# P20-Receptor_Transmisor_NRF24I01.net
KiCad netlist of a schematic drawn in EAGLE
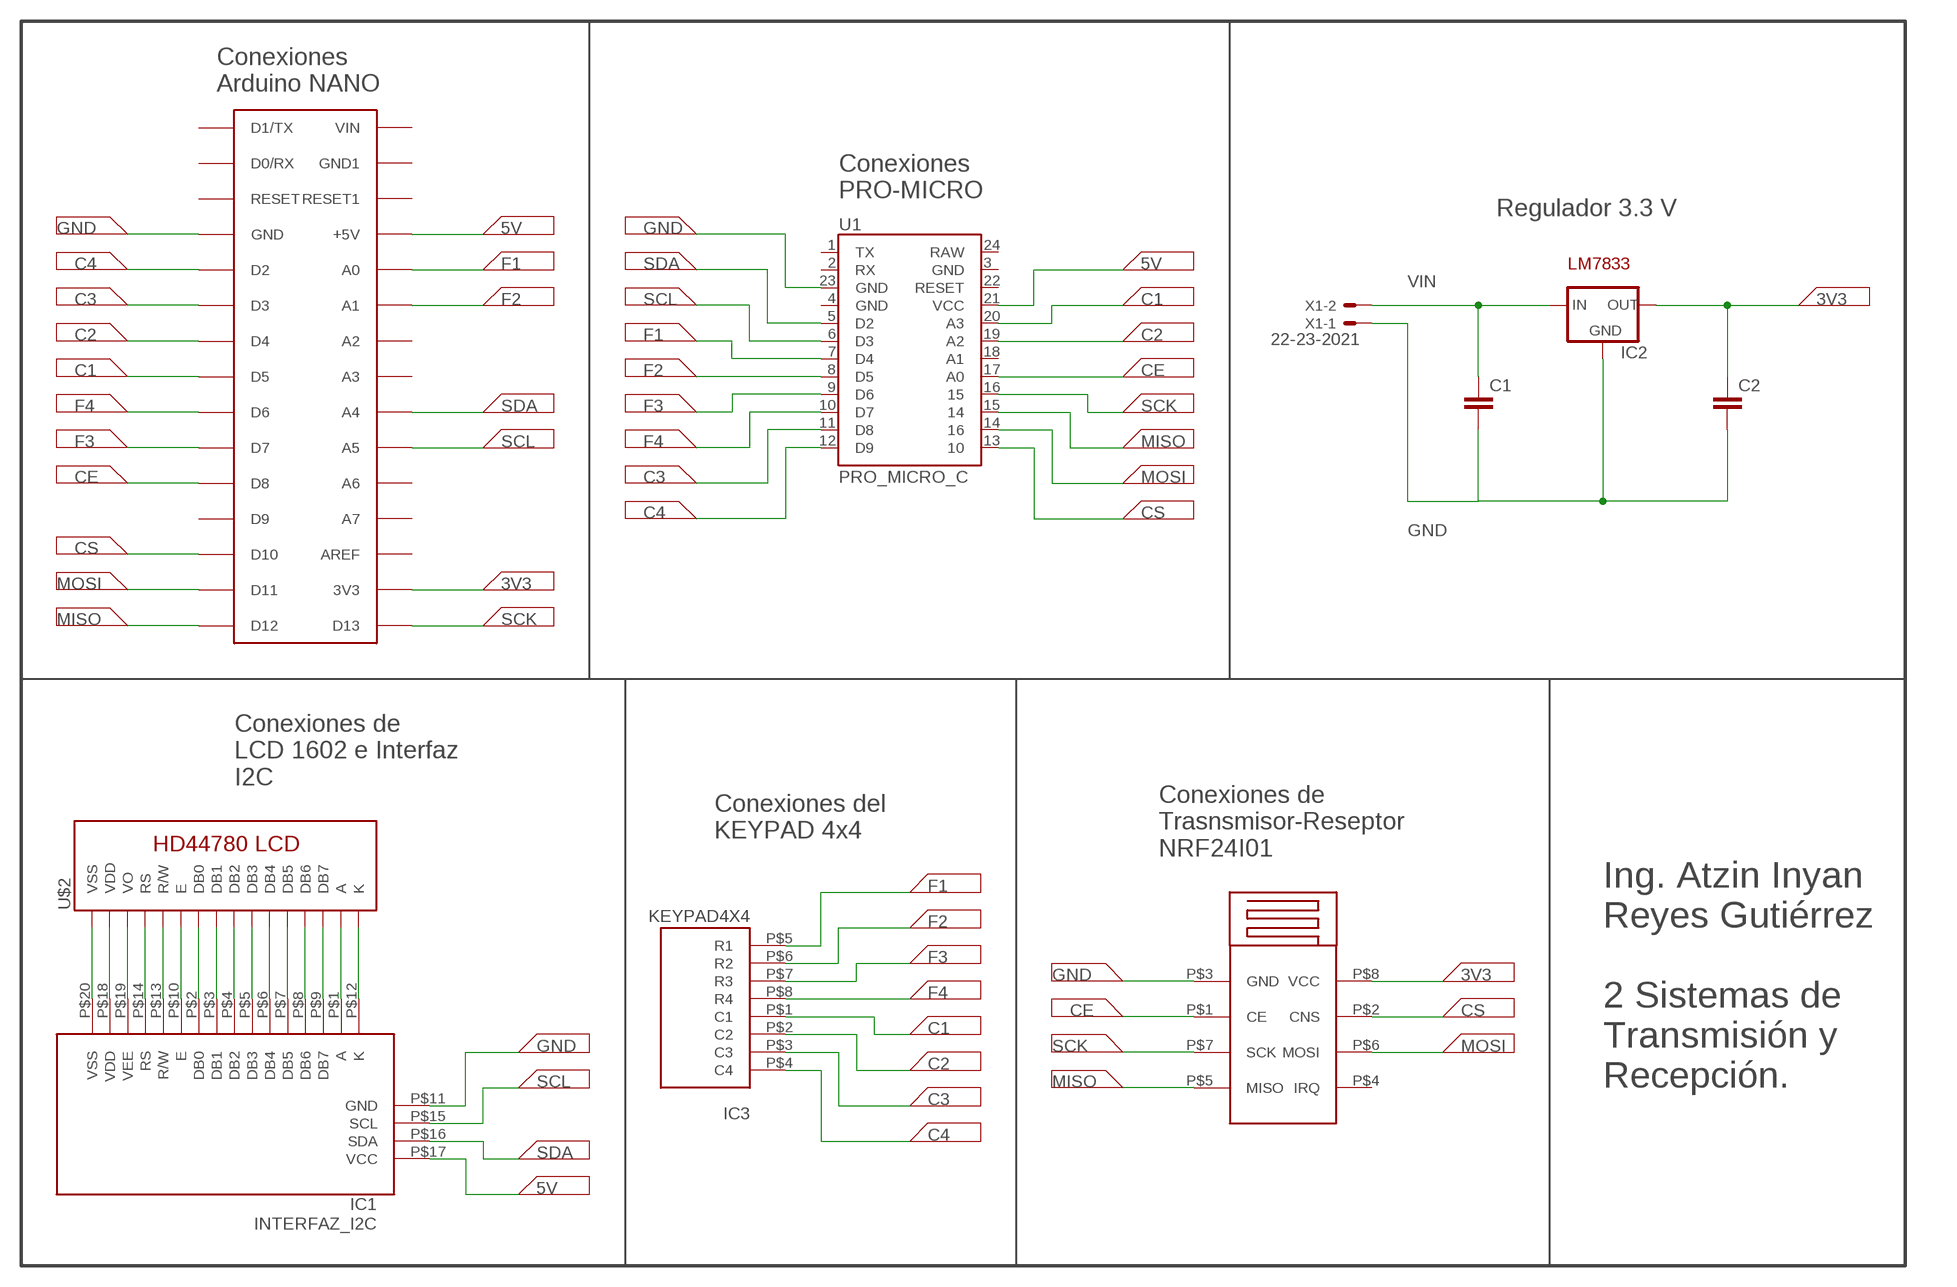
[diagram p0: schematic, sheet 1]

(export (version "E")
  (design (tool "Eeschema 10.0.6"))
  (components
    (comp (ref "C1")
      (value "C2,5-3")
      (footprint "eagle-import:C2.5-3")
      (libsource (lib "eagle-import") (part "C2,5-3"))
    )
    (comp (ref "C2")
      (value "C2,5-3")
      (footprint "eagle-import:C2.5-3")
      (libsource (lib "eagle-import") (part "C2,5-3"))
    )
    (comp (ref "IC1")
      (value "INTERFAZ_I2C")
      (footprint "eagle-import:NO_FOOTPRINT")
      (libsource (lib "eagle-import") (part "INTERFAZ_I2C"))
    )
    (comp (ref "IC2")
      (value "78MXXL")
      (footprint "eagle-import:78MXXL")
      (libsource (lib "eagle-import") (part "78MXXL"))
    )
    (comp (ref "IC3")
      (value "KEYPAD4X4")
      (footprint "eagle-import:NO_FOOTPRINT")
      (libsource (lib "eagle-import") (part "KEYPAD4X4"))
    )
    (comp (ref "U$1")
      (value "ARDUINONANO")
      (footprint "eagle-import:PDIP-32")
      (libsource (lib "eagle-import") (part "ARDUINONANO"))
    )
    (comp (ref "U$2")
      (value "LCD-HD447803-HOLES16X2-3-HOLES")
      (footprint "eagle-import:LCD-16X2-3HOLES")
      (libsource (lib "eagle-import") (part "LCD-HD4478016X2-3-HOLES3-HOLES"))
    )
    (comp (ref "U$3")
      (value "NRF24I01")
      (footprint "eagle-import:NOT_FOOTPRINT")
      (libsource (lib "eagle-import") (part "NRF24I01"))
    )
    (comp (ref "U1")
      (value "PRO_MICRO_C")
      (footprint "eagle-import:PRO_MICRO_C")
      (libsource (lib "eagle-import") (part "PRO_MICRO_C"))
    )
    (comp (ref "X1")
      (value "22-23-2021")
      (footprint "eagle-import:22-23-2021")
      (fields (field (name "MF") "MOLEX"))
      (libsource (lib "eagle-import") (part "22-23-2021"))
    )
  )
  (nets
    (net (code "1") (name "/3V3") (class "Default")
      (node (ref "C2") (pin "1") (pinfunction "1_1") (pintype "passive"))
      (node (ref "IC2") (pin "OUT") (pinfunction "OUT_OUT") (pintype "passive"))
      (node (ref "U$1") (pin "3V3") (pinfunction "3V3_3V3") (pintype "bidirectional"))
      (node (ref "U$3") (pin "P$8") (pinfunction "VCC_P$8") (pintype "bidirectional"))
    )
    (net (code "2") (name "/5V") (class "Default")
      (node (ref "IC1") (pin "P$17") (pinfunction "VCC_P$17") (pintype "bidirectional"))
      (node (ref "U$1") (pin "+5V") (pinfunction "+5V_+5V") (pintype "bidirectional"))
      (node (ref "U1") (pin "21") (pinfunction "VCC_21") (pintype "bidirectional"))
    )
    (net (code "3") (name "/C1") (class "Default")
      (node (ref "IC3") (pin "P$1") (pinfunction "C1_P$1") (pintype "bidirectional"))
      (node (ref "U$1") (pin "D5") (pinfunction "D5_D5") (pintype "bidirectional"))
      (node (ref "U1") (pin "20") (pinfunction "A3_20") (pintype "bidirectional"))
    )
    (net (code "4") (name "/C2") (class "Default")
      (node (ref "IC3") (pin "P$2") (pinfunction "C2_P$2") (pintype "bidirectional"))
      (node (ref "U$1") (pin "D4") (pinfunction "D4_D4") (pintype "bidirectional"))
      (node (ref "U1") (pin "19") (pinfunction "A2_19") (pintype "bidirectional"))
    )
    (net (code "5") (name "/C3") (class "Default")
      (node (ref "IC3") (pin "P$3") (pinfunction "C3_P$3") (pintype "bidirectional"))
      (node (ref "U$1") (pin "D3") (pinfunction "D3_D3") (pintype "bidirectional"))
      (node (ref "U1") (pin "11") (pinfunction "D8_11") (pintype "bidirectional"))
    )
    (net (code "6") (name "/C4") (class "Default")
      (node (ref "IC3") (pin "P$4") (pinfunction "C4_P$4") (pintype "bidirectional"))
      (node (ref "U$1") (pin "D2") (pinfunction "D2_D2") (pintype "bidirectional"))
      (node (ref "U1") (pin "12") (pinfunction "D9_12") (pintype "bidirectional"))
    )
    (net (code "7") (name "/CE") (class "Default")
      (node (ref "U$1") (pin "D8") (pinfunction "D8_D8") (pintype "bidirectional"))
      (node (ref "U$3") (pin "P$1") (pinfunction "CE_P$1") (pintype "bidirectional"))
      (node (ref "U1") (pin "17") (pinfunction "A0_17") (pintype "bidirectional"))
    )
    (net (code "8") (name "/CS") (class "Default")
      (node (ref "U$1") (pin "D10") (pinfunction "D10_D10") (pintype "bidirectional"))
      (node (ref "U$3") (pin "P$2") (pinfunction "CNS_P$2") (pintype "bidirectional"))
      (node (ref "U1") (pin "13") (pinfunction "10_13") (pintype "bidirectional"))
    )
    (net (code "9") (name "/F1") (class "Default")
      (node (ref "IC3") (pin "P$5") (pinfunction "R1_P$5") (pintype "bidirectional"))
      (node (ref "U$1") (pin "A0") (pinfunction "A0_A0") (pintype "bidirectional"))
      (node (ref "U1") (pin "7") (pinfunction "D4_7") (pintype "bidirectional"))
    )
    (net (code "10") (name "/F2") (class "Default")
      (node (ref "IC3") (pin "P$6") (pinfunction "R2_P$6") (pintype "bidirectional"))
      (node (ref "U$1") (pin "A1") (pinfunction "A1_A1") (pintype "bidirectional"))
      (node (ref "U1") (pin "8") (pinfunction "D5_8") (pintype "bidirectional"))
    )
    (net (code "11") (name "/F3") (class "Default")
      (node (ref "IC3") (pin "P$7") (pinfunction "R3_P$7") (pintype "bidirectional"))
      (node (ref "U$1") (pin "D7") (pinfunction "D7_D7") (pintype "bidirectional"))
      (node (ref "U1") (pin "9") (pinfunction "D6_9") (pintype "bidirectional"))
    )
    (net (code "12") (name "/F4") (class "Default")
      (node (ref "IC3") (pin "P$8") (pinfunction "R4_P$8") (pintype "bidirectional"))
      (node (ref "U$1") (pin "D6") (pinfunction "D6_D6") (pintype "bidirectional"))
      (node (ref "U1") (pin "10") (pinfunction "D7_10") (pintype "bidirectional"))
    )
    (net (code "13") (name "/GND") (class "Default")
      (node (ref "C1") (pin "2") (pinfunction "2_2") (pintype "passive"))
      (node (ref "C2") (pin "2") (pinfunction "2_2") (pintype "passive"))
      (node (ref "IC1") (pin "P$11") (pinfunction "GND_P$11") (pintype "bidirectional"))
      (node (ref "IC2") (pin "GND") (pinfunction "GND_GND") (pintype "input"))
      (node (ref "U$1") (pin "GND") (pinfunction "GND_GND") (pintype "bidirectional"))
      (node (ref "U$3") (pin "P$3") (pinfunction "GND_P$3") (pintype "bidirectional"))
      (node (ref "U1") (pin "23") (pinfunction "GND_23") (pintype "bidirectional"))
      (node (ref "X1") (pin "1") (pinfunction "S_1") (pintype "passive"))
    )
    (net (code "14") (name "/MISO") (class "Default")
      (node (ref "U$1") (pin "D12") (pinfunction "D12_D12") (pintype "bidirectional"))
      (node (ref "U$3") (pin "P$5") (pinfunction "MISO_P$5") (pintype "bidirectional"))
      (node (ref "U1") (pin "15") (pinfunction "14_15") (pintype "bidirectional"))
    )
    (net (code "15") (name "/MOSI") (class "Default")
      (node (ref "U$1") (pin "D11") (pinfunction "D11_D11") (pintype "bidirectional"))
      (node (ref "U$3") (pin "P$6") (pinfunction "MOSI_P$6") (pintype "bidirectional"))
      (node (ref "U1") (pin "14") (pinfunction "16_14") (pintype "bidirectional"))
    )
    (net (code "16") (name "/SCK") (class "Default")
      (node (ref "U$1") (pin "D13") (pinfunction "D13_D13") (pintype "bidirectional"))
      (node (ref "U$3") (pin "P$7") (pinfunction "SCK_P$7") (pintype "bidirectional"))
      (node (ref "U1") (pin "16") (pinfunction "15_16") (pintype "bidirectional"))
    )
    (net (code "17") (name "/SCL") (class "Default")
      (node (ref "IC1") (pin "P$15") (pinfunction "SCL_P$15") (pintype "bidirectional"))
      (node (ref "U$1") (pin "A5") (pinfunction "A5_A5") (pintype "bidirectional"))
      (node (ref "U1") (pin "6") (pinfunction "D3_6") (pintype "bidirectional"))
    )
    (net (code "18") (name "/SDA") (class "Default")
      (node (ref "IC1") (pin "P$16") (pinfunction "SDA_P$16") (pintype "bidirectional"))
      (node (ref "U$1") (pin "A4") (pinfunction "A4_A4") (pintype "bidirectional"))
      (node (ref "U1") (pin "5") (pinfunction "D2_5") (pintype "bidirectional"))
    )
    (net (code "19") (name "/VIN") (class "Default")
      (node (ref "C1") (pin "1") (pinfunction "1_1") (pintype "passive"))
      (node (ref "IC2") (pin "IN") (pinfunction "IN_IN") (pintype "input"))
      (node (ref "X1") (pin "2") (pinfunction "S_2") (pintype "passive"))
    )
    (net (code "20") (name "Net-(IC1-A)") (class "Default")
      (node (ref "IC1") (pin "P$1") (pinfunction "A_P$1") (pintype "bidirectional"))
      (node (ref "U$2") (pin "15") (pinfunction "A_15") (pintype "power_in"))
    )
    (net (code "21") (name "Net-(IC1-DB0)") (class "Default")
      (node (ref "IC1") (pin "P$2") (pinfunction "DB0_P$2") (pintype "bidirectional"))
      (node (ref "U$2") (pin "7") (pinfunction "DB0_7") (pintype "bidirectional"))
    )
    (net (code "22") (name "Net-(IC1-DB1)") (class "Default")
      (node (ref "IC1") (pin "P$3") (pinfunction "DB1_P$3") (pintype "bidirectional"))
      (node (ref "U$2") (pin "8") (pinfunction "DB1_8") (pintype "bidirectional"))
    )
    (net (code "23") (name "Net-(IC1-DB2)") (class "Default")
      (node (ref "IC1") (pin "P$4") (pinfunction "DB2_P$4") (pintype "bidirectional"))
      (node (ref "U$2") (pin "9") (pinfunction "DB2_9") (pintype "bidirectional"))
    )
    (net (code "24") (name "Net-(IC1-DB3)") (class "Default")
      (node (ref "IC1") (pin "P$5") (pinfunction "DB3_P$5") (pintype "bidirectional"))
      (node (ref "U$2") (pin "10") (pinfunction "DB3_10") (pintype "bidirectional"))
    )
    (net (code "25") (name "Net-(IC1-DB4)") (class "Default")
      (node (ref "IC1") (pin "P$6") (pinfunction "DB4_P$6") (pintype "bidirectional"))
      (node (ref "U$2") (pin "11") (pinfunction "DB4_11") (pintype "bidirectional"))
    )
    (net (code "26") (name "Net-(IC1-DB5)") (class "Default")
      (node (ref "IC1") (pin "P$7") (pinfunction "DB5_P$7") (pintype "bidirectional"))
      (node (ref "U$2") (pin "12") (pinfunction "DB5_12") (pintype "bidirectional"))
    )
    (net (code "27") (name "Net-(IC1-DB6)") (class "Default")
      (node (ref "IC1") (pin "P$8") (pinfunction "DB6_P$8") (pintype "bidirectional"))
      (node (ref "U$2") (pin "13") (pinfunction "DB6_13") (pintype "bidirectional"))
    )
    (net (code "28") (name "Net-(IC1-DB7)") (class "Default")
      (node (ref "IC1") (pin "P$9") (pinfunction "DB7_P$9") (pintype "bidirectional"))
      (node (ref "U$2") (pin "14") (pinfunction "DB7_14") (pintype "bidirectional"))
    )
    (net (code "29") (name "Net-(IC1-E)") (class "Default")
      (node (ref "IC1") (pin "P$10") (pinfunction "E_P$10") (pintype "bidirectional"))
      (node (ref "U$2") (pin "6") (pinfunction "E_6") (pintype "input"))
    )
    (net (code "30") (name "Net-(IC1-K)") (class "Default")
      (node (ref "IC1") (pin "P$12") (pinfunction "K_P$12") (pintype "bidirectional"))
      (node (ref "U$2") (pin "16") (pinfunction "K_16") (pintype "power_in"))
    )
    (net (code "31") (name "Net-(IC1-RS)") (class "Default")
      (node (ref "IC1") (pin "P$14") (pinfunction "RS_P$14") (pintype "bidirectional"))
      (node (ref "U$2") (pin "4") (pinfunction "RS_4") (pintype "input"))
    )
    (net (code "32") (name "Net-(IC1-R{slash}W)") (class "Default")
      (node (ref "IC1") (pin "P$13") (pinfunction "R/W_P$13") (pintype "bidirectional"))
      (node (ref "U$2") (pin "5") (pinfunction "R/W_5") (pintype "input"))
    )
    (net (code "33") (name "Net-(IC1-VDD)") (class "Default")
      (node (ref "IC1") (pin "P$18") (pinfunction "VDD_P$18") (pintype "bidirectional"))
      (node (ref "U$2") (pin "2") (pinfunction "VDD_2") (pintype "power_in"))
    )
    (net (code "34") (name "Net-(IC1-VEE)") (class "Default")
      (node (ref "IC1") (pin "P$19") (pinfunction "VEE_P$19") (pintype "bidirectional"))
      (node (ref "U$2") (pin "3") (pinfunction "VO_3") (pintype "bidirectional"))
    )
    (net (code "35") (name "Net-(IC1-VSS)") (class "Default")
      (node (ref "IC1") (pin "P$20") (pinfunction "VSS_P$20") (pintype "bidirectional"))
      (node (ref "U$2") (pin "1") (pinfunction "VSS_1") (pintype "power_in"))
    )
    (net (code "36") (name "unconnected-(U$1-PadA2)") (class "Default")
      (node (ref "U$1") (pin "A2") (pinfunction "A2_A2") (pintype "bidirectional"))
    )
    (net (code "37") (name "unconnected-(U$1-PadA3)") (class "Default")
      (node (ref "U$1") (pin "A3") (pinfunction "A3_A3") (pintype "bidirectional"))
    )
    (net (code "38") (name "unconnected-(U$1-PadA6)") (class "Default")
      (node (ref "U$1") (pin "A6") (pinfunction "A6_A6") (pintype "bidirectional"))
    )
    (net (code "39") (name "unconnected-(U$1-PadA7)") (class "Default")
      (node (ref "U$1") (pin "A7") (pinfunction "A7_A7") (pintype "bidirectional"))
    )
    (net (code "40") (name "unconnected-(U$1-PadAREF)") (class "Default")
      (node (ref "U$1") (pin "AREF") (pinfunction "AREF_AREF") (pintype "bidirectional"))
    )
    (net (code "41") (name "unconnected-(U$1-PadD0{slash}RX)") (class "Default")
      (node (ref "U$1") (pin "D0/RX") (pinfunction "D0/RX_D0/RX") (pintype "bidirectional"))
    )
    (net (code "42") (name "unconnected-(U$1-PadD1{slash}TX)") (class "Default")
      (node (ref "U$1") (pin "D1/TX") (pinfunction "D1/TX_D1/TX") (pintype "bidirectional"))
    )
    (net (code "43") (name "unconnected-(U$1-PadD9)") (class "Default")
      (node (ref "U$1") (pin "D9") (pinfunction "D9_D9") (pintype "bidirectional"))
    )
    (net (code "44") (name "unconnected-(U$1-PadGND1)") (class "Default")
      (node (ref "U$1") (pin "GND1") (pinfunction "GND1_GND1") (pintype "bidirectional"))
    )
    (net (code "45") (name "unconnected-(U$1-PadRESET)") (class "Default")
      (node (ref "U$1") (pin "RESET") (pinfunction "RESET_RESET") (pintype "bidirectional"))
    )
    (net (code "46") (name "unconnected-(U$1-PadRESET1)") (class "Default")
      (node (ref "U$1") (pin "RESET1") (pinfunction "RESET1_RESET1") (pintype "bidirectional"))
    )
    (net (code "47") (name "unconnected-(U$1-PadVIN)") (class "Default")
      (node (ref "U$1") (pin "VIN") (pinfunction "VIN_VIN") (pintype "bidirectional"))
    )
    (net (code "48") (name "unconnected-(U$3-IRQ-PadP$4)") (class "Default")
      (node (ref "U$3") (pin "P$4") (pinfunction "IRQ_P$4") (pintype "bidirectional"))
    )
    (net (code "49") (name "unconnected-(U1-A1-Pad18)") (class "Default")
      (node (ref "U1") (pin "18") (pinfunction "A1_18") (pintype "bidirectional"))
    )
    (net (code "50") (name "unconnected-(U1-GND-Pad3)") (class "Default")
      (node (ref "U1") (pin "3") (pinfunction "GND_3") (pintype "bidirectional"))
    )
    (net (code "51") (name "unconnected-(U1-GND-Pad4)") (class "Default")
      (node (ref "U1") (pin "4") (pinfunction "GND_4") (pintype "bidirectional"))
    )
    (net (code "52") (name "unconnected-(U1-RAW-Pad24)") (class "Default")
      (node (ref "U1") (pin "24") (pinfunction "RAW_24") (pintype "bidirectional"))
    )
    (net (code "53") (name "unconnected-(U1-RESET-Pad22)") (class "Default")
      (node (ref "U1") (pin "22") (pinfunction "RESET_22") (pintype "bidirectional"))
    )
    (net (code "54") (name "unconnected-(U1-RX-Pad2)") (class "Default")
      (node (ref "U1") (pin "2") (pinfunction "RX_2") (pintype "bidirectional"))
    )
    (net (code "55") (name "unconnected-(U1-TX-Pad1)") (class "Default")
      (node (ref "U1") (pin "1") (pinfunction "TX_1") (pintype "bidirectional"))
    )
  )
)
